# loom-rear-LV-box.net
KiCad netlist of a schematic drawn in Altium Designer
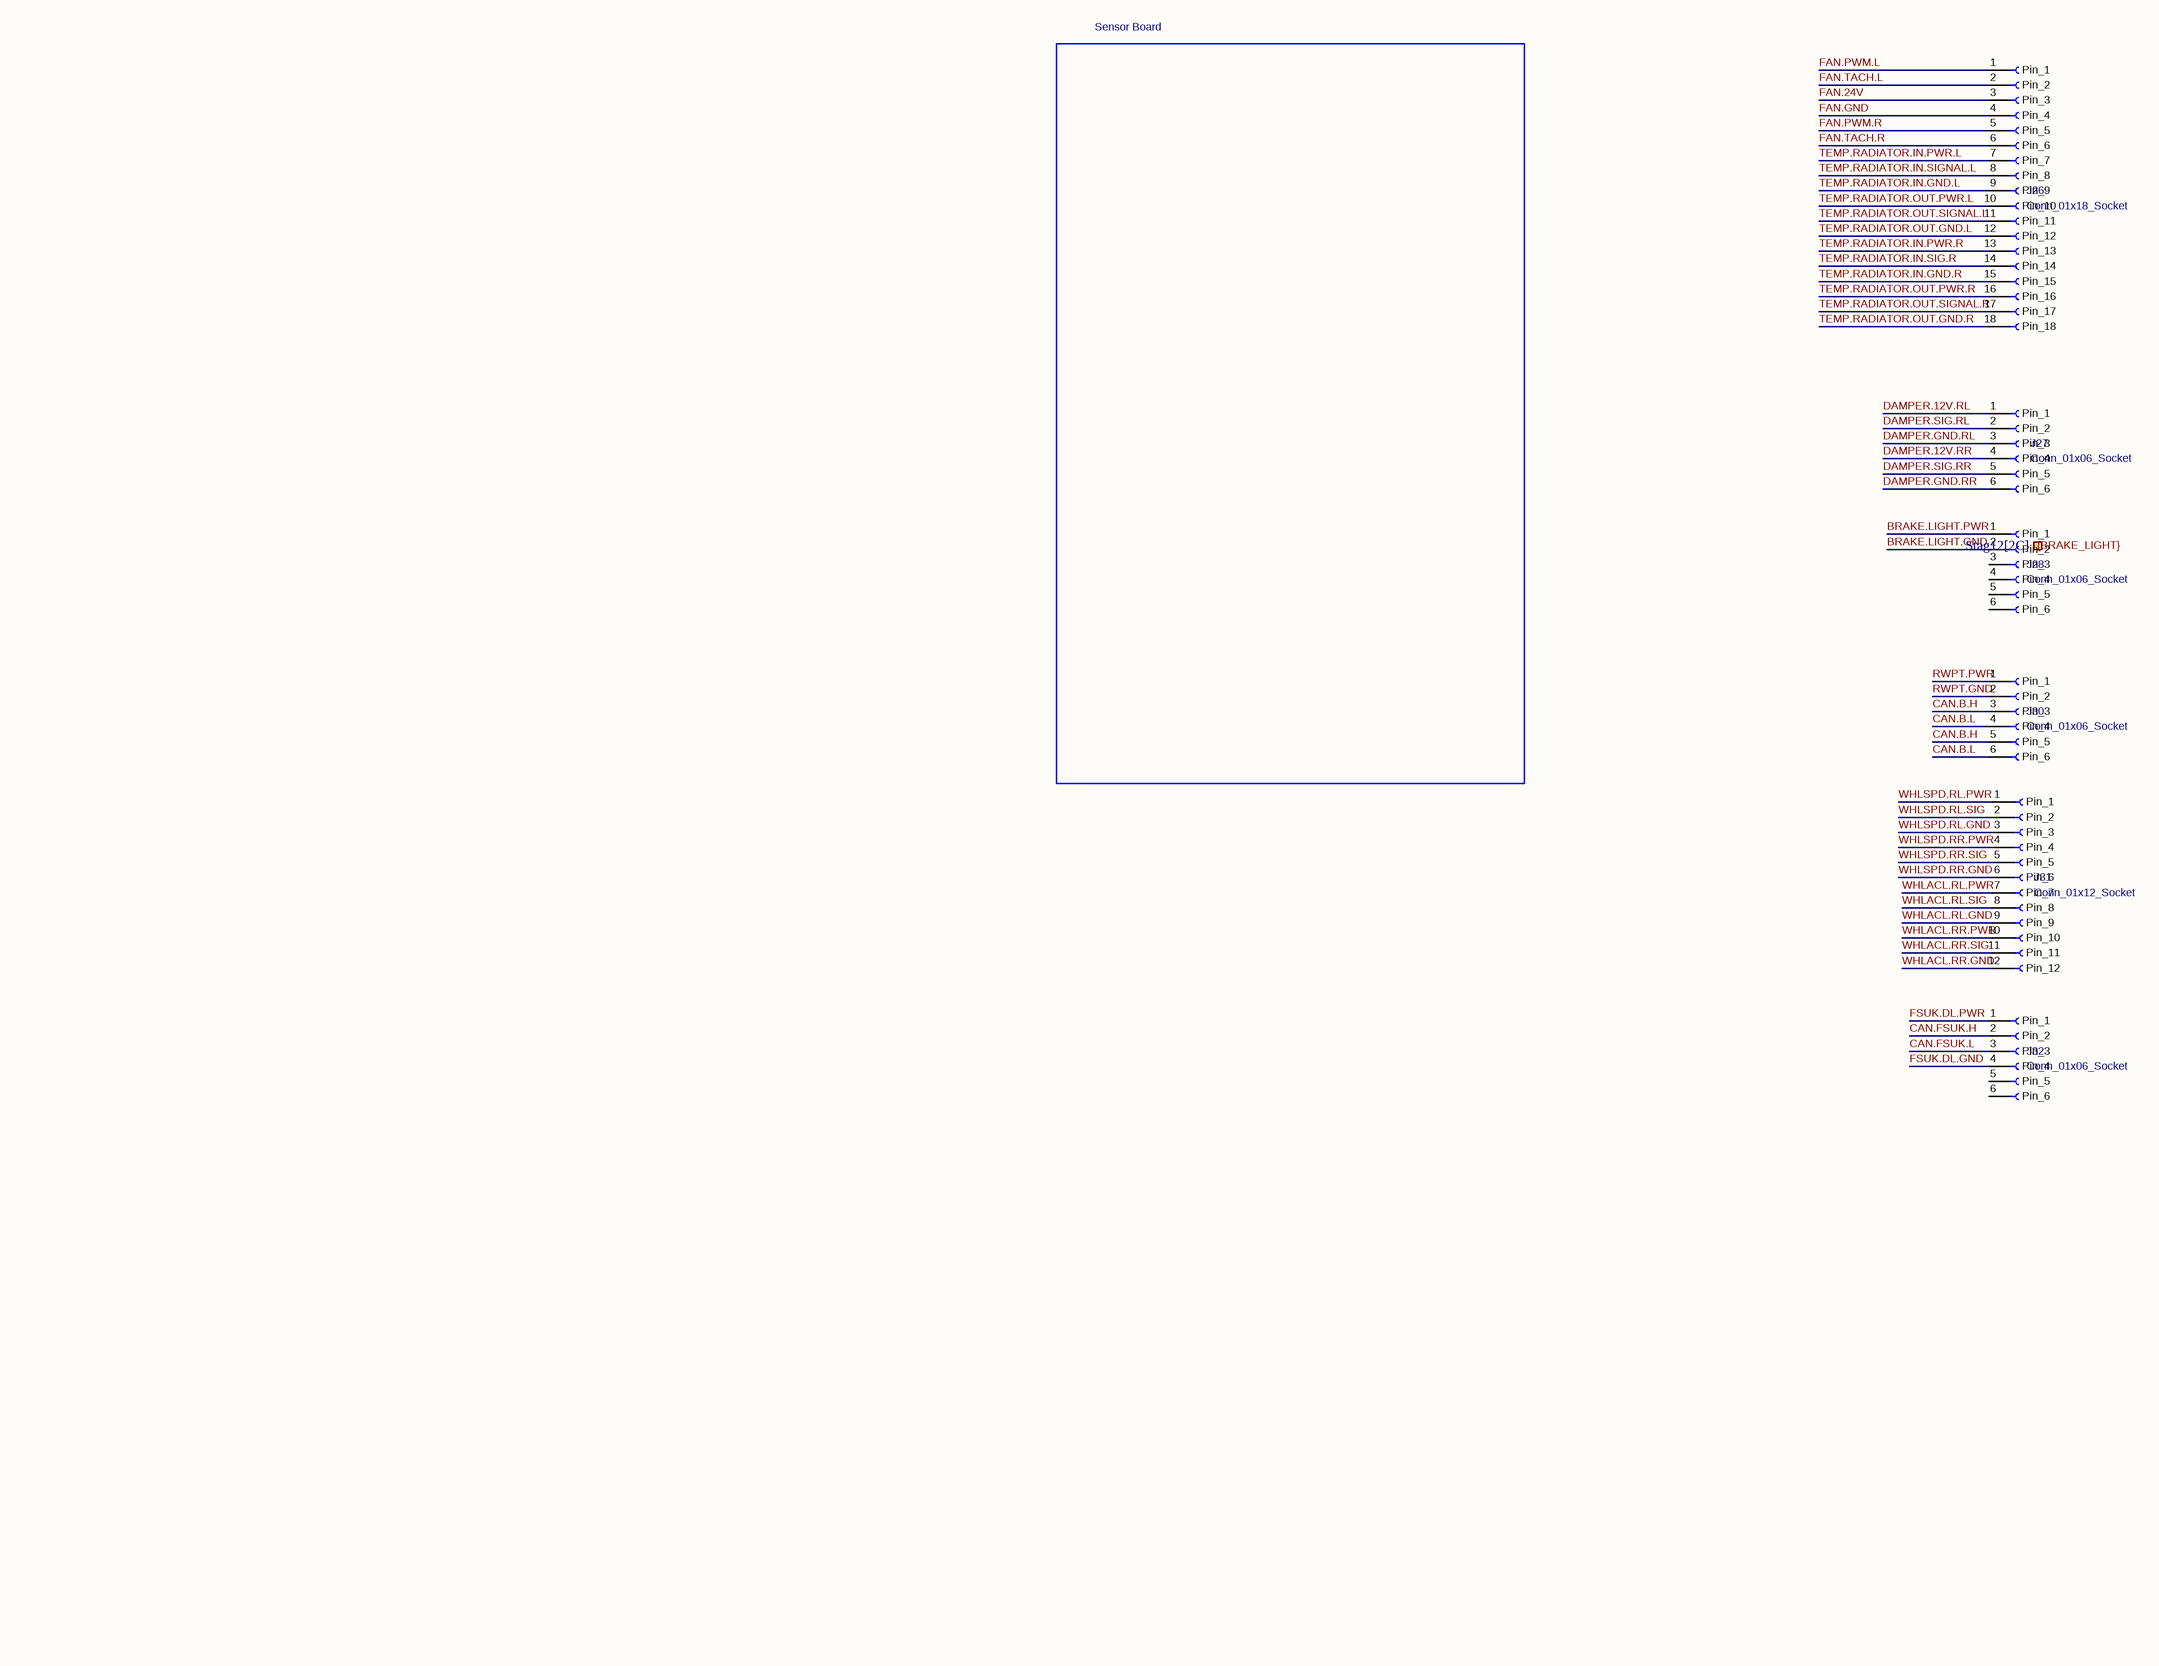
[diagram p0: loom-rear-LV-box.SchDoc]

(export (version "E")
  (design (tool "Eeschema 10.0.6"))
  (components
    (comp (ref "J26") (value "Conn_01x18_Socket") (libsource (lib "Connector") (part "Conn_01x18_Socket")))
    (comp (ref "J27") (value "Conn_01x06_Socket") (libsource (lib "Connector") (part "Conn_01x06_Socket")))
    (comp (ref "J28") (value "Conn_01x06_Socket") (libsource (lib "Connector") (part "Conn_01x06_Socket")))
    (comp (ref "J30") (value "Conn_01x06_Socket") (libsource (lib "Connector") (part "Conn_01x06_Socket")))
    (comp (ref "J31") (value "Conn_01x12_Socket") (libsource (lib "Connector") (part "Conn_01x12_Socket")))
    (comp (ref "J32") (value "Conn_01x06_Socket") (libsource (lib "Connector") (part "Conn_01x06_Socket")))
  )
  (nets
    (net (code "2") (name "/BRAKE.LIGHT.GND") (class "Default")
      (node (ref "J28") (pin "2") (pinfunction "Pin_2_2") (pintype "passive"))
    )
    (net (code "3") (name "/BRAKE.LIGHT.PWR") (class "Default")
      (node (ref "J28") (pin "1") (pinfunction "Pin_1_1") (pintype "passive"))
    )
    (net (code "4") (name "/CAN.B.H") (class "Default")
      (node (ref "J30") (pin "3") (pinfunction "Pin_3_3") (pintype "passive"))
      (node (ref "J30") (pin "5") (pinfunction "Pin_5_5") (pintype "passive"))
    )
    (net (code "5") (name "/CAN.B.L") (class "Default")
      (node (ref "J30") (pin "4") (pinfunction "Pin_4_4") (pintype "passive"))
      (node (ref "J30") (pin "6") (pinfunction "Pin_6_6") (pintype "passive"))
    )
    (net (code "6") (name "/CAN.FSUK.H") (class "Default")
      (node (ref "J32") (pin "2") (pinfunction "Pin_2_2") (pintype "passive"))
    )
    (net (code "7") (name "/CAN.FSUK.L") (class "Default")
      (node (ref "J32") (pin "3") (pinfunction "Pin_3_3") (pintype "passive"))
    )
    (net (code "8") (name "/DAMPER.12V.RL") (class "Default")
      (node (ref "J27") (pin "1") (pinfunction "Pin_1_1") (pintype "passive"))
    )
    (net (code "9") (name "/DAMPER.12V.RR") (class "Default")
      (node (ref "J27") (pin "4") (pinfunction "Pin_4_4") (pintype "passive"))
    )
    (net (code "10") (name "/DAMPER.GND.RL") (class "Default")
      (node (ref "J27") (pin "3") (pinfunction "Pin_3_3") (pintype "passive"))
    )
    (net (code "11") (name "/DAMPER.GND.RR") (class "Default")
      (node (ref "J27") (pin "6") (pinfunction "Pin_6_6") (pintype "passive"))
    )
    (net (code "12") (name "/DAMPER.SIG.RL") (class "Default")
      (node (ref "J27") (pin "2") (pinfunction "Pin_2_2") (pintype "passive"))
    )
    (net (code "13") (name "/DAMPER.SIG.RR") (class "Default")
      (node (ref "J27") (pin "5") (pinfunction "Pin_5_5") (pintype "passive"))
    )
    (net (code "14") (name "/FAN.24V") (class "Default")
      (node (ref "J26") (pin "3") (pinfunction "Pin_3_3") (pintype "passive"))
    )
    (net (code "15") (name "/FAN.GND") (class "Default")
      (node (ref "J26") (pin "4") (pinfunction "Pin_4_4") (pintype "passive"))
    )
    (net (code "16") (name "/FAN.PWM.L") (class "Default")
      (node (ref "J26") (pin "1") (pinfunction "Pin_1_1") (pintype "passive"))
    )
    (net (code "17") (name "/FAN.PWM.R") (class "Default")
      (node (ref "J26") (pin "5") (pinfunction "Pin_5_5") (pintype "passive"))
    )
    (net (code "18") (name "/FAN.TACH.L") (class "Default")
      (node (ref "J26") (pin "2") (pinfunction "Pin_2_2") (pintype "passive"))
    )
    (net (code "19") (name "/FAN.TACH.R") (class "Default")
      (node (ref "J26") (pin "6") (pinfunction "Pin_6_6") (pintype "passive"))
    )
    (net (code "20") (name "/FSUK.DL.GND") (class "Default")
      (node (ref "J32") (pin "4") (pinfunction "Pin_4_4") (pintype "passive"))
    )
    (net (code "21") (name "/FSUK.DL.PWR") (class "Default")
      (node (ref "J32") (pin "1") (pinfunction "Pin_1_1") (pintype "passive"))
    )
    (net (code "22") (name "/RWPT.GND") (class "Default")
      (node (ref "J30") (pin "2") (pinfunction "Pin_2_2") (pintype "passive"))
    )
    (net (code "23") (name "/RWPT.PWR") (class "Default")
      (node (ref "J30") (pin "1") (pinfunction "Pin_1_1") (pintype "passive"))
    )
    (net (code "24") (name "/TEMP.RADIATOR.IN.GND.L") (class "Default")
      (node (ref "J26") (pin "9") (pinfunction "Pin_9_9") (pintype "passive"))
    )
    (net (code "25") (name "/TEMP.RADIATOR.IN.GND.R") (class "Default")
      (node (ref "J26") (pin "15") (pinfunction "Pin_15_15") (pintype "passive"))
    )
    (net (code "26") (name "/TEMP.RADIATOR.IN.PWR.L") (class "Default")
      (node (ref "J26") (pin "7") (pinfunction "Pin_7_7") (pintype "passive"))
    )
    (net (code "27") (name "/TEMP.RADIATOR.IN.PWR.R") (class "Default")
      (node (ref "J26") (pin "13") (pinfunction "Pin_13_13") (pintype "passive"))
    )
    (net (code "28") (name "/TEMP.RADIATOR.IN.SIG.R") (class "Default")
      (node (ref "J26") (pin "14") (pinfunction "Pin_14_14") (pintype "passive"))
    )
    (net (code "29") (name "/TEMP.RADIATOR.IN.SIGNAL.L") (class "Default")
      (node (ref "J26") (pin "8") (pinfunction "Pin_8_8") (pintype "passive"))
    )
    (net (code "30") (name "/TEMP.RADIATOR.OUT.GND.L") (class "Default")
      (node (ref "J26") (pin "12") (pinfunction "Pin_12_12") (pintype "passive"))
    )
    (net (code "31") (name "/TEMP.RADIATOR.OUT.GND.R") (class "Default")
      (node (ref "J26") (pin "18") (pinfunction "Pin_18_18") (pintype "passive"))
    )
    (net (code "32") (name "/TEMP.RADIATOR.OUT.PWR.L") (class "Default")
      (node (ref "J26") (pin "10") (pinfunction "Pin_10_10") (pintype "passive"))
    )
    (net (code "33") (name "/TEMP.RADIATOR.OUT.PWR.R") (class "Default")
      (node (ref "J26") (pin "16") (pinfunction "Pin_16_16") (pintype "passive"))
    )
    (net (code "34") (name "/TEMP.RADIATOR.OUT.SIGNAL.L") (class "Default")
      (node (ref "J26") (pin "11") (pinfunction "Pin_11_11") (pintype "passive"))
    )
    (net (code "35") (name "/TEMP.RADIATOR.OUT.SIGNAL.R") (class "Default")
      (node (ref "J26") (pin "17") (pinfunction "Pin_17_17") (pintype "passive"))
    )
    (net (code "36") (name "/WHLACL.RL.GND") (class "Default")
      (node (ref "J31") (pin "9") (pinfunction "Pin_9_9") (pintype "passive"))
    )
    (net (code "37") (name "/WHLACL.RL.PWR") (class "Default")
      (node (ref "J31") (pin "7") (pinfunction "Pin_7_7") (pintype "passive"))
    )
    (net (code "38") (name "/WHLACL.RL.SIG") (class "Default")
      (node (ref "J31") (pin "8") (pinfunction "Pin_8_8") (pintype "passive"))
    )
    (net (code "39") (name "/WHLACL.RR.GND") (class "Default")
      (node (ref "J31") (pin "12") (pinfunction "Pin_12_12") (pintype "passive"))
    )
    (net (code "40") (name "/WHLACL.RR.PWR") (class "Default")
      (node (ref "J31") (pin "10") (pinfunction "Pin_10_10") (pintype "passive"))
    )
    (net (code "41") (name "/WHLACL.RR.SIG") (class "Default")
      (node (ref "J31") (pin "11") (pinfunction "Pin_11_11") (pintype "passive"))
    )
    (net (code "42") (name "/WHLSPD.RL.GND") (class "Default")
      (node (ref "J31") (pin "3") (pinfunction "Pin_3_3") (pintype "passive"))
    )
    (net (code "43") (name "/WHLSPD.RL.PWR") (class "Default")
      (node (ref "J31") (pin "1") (pinfunction "Pin_1_1") (pintype "passive"))
    )
    (net (code "44") (name "/WHLSPD.RL.SIG") (class "Default")
      (node (ref "J31") (pin "2") (pinfunction "Pin_2_2") (pintype "passive"))
    )
    (net (code "45") (name "/WHLSPD.RR.GND") (class "Default")
      (node (ref "J31") (pin "6") (pinfunction "Pin_6_6") (pintype "passive"))
    )
    (net (code "46") (name "/WHLSPD.RR.PWR") (class "Default")
      (node (ref "J31") (pin "4") (pinfunction "Pin_4_4") (pintype "passive"))
    )
    (net (code "47") (name "/WHLSPD.RR.SIG") (class "Default")
      (node (ref "J31") (pin "5") (pinfunction "Pin_5_5") (pintype "passive"))
    )
    (net (code "49") (name "unconnected-(J28-Pin_3-Pad3)") (class "Default")
      (node (ref "J28") (pin "3") (pinfunction "Pin_3_3") (pintype "passive"))
    )
    (net (code "50") (name "unconnected-(J28-Pin_4-Pad4)") (class "Default")
      (node (ref "J28") (pin "4") (pinfunction "Pin_4_4") (pintype "passive"))
    )
    (net (code "51") (name "unconnected-(J28-Pin_5-Pad5)") (class "Default")
      (node (ref "J28") (pin "5") (pinfunction "Pin_5_5") (pintype "passive"))
    )
    (net (code "52") (name "unconnected-(J28-Pin_6-Pad6)") (class "Default")
      (node (ref "J28") (pin "6") (pinfunction "Pin_6_6") (pintype "passive"))
    )
    (net (code "53") (name "unconnected-(J32-Pin_5-Pad5)") (class "Default")
      (node (ref "J32") (pin "5") (pinfunction "Pin_5_5") (pintype "passive"))
    )
    (net (code "54") (name "unconnected-(J32-Pin_6-Pad6)") (class "Default")
      (node (ref "J32") (pin "6") (pinfunction "Pin_6_6") (pintype "passive"))
    )
  )
)
